# Exp_Board_RAMPS_0_1.net
KiCad netlist of a schematic drawn in EAGLE
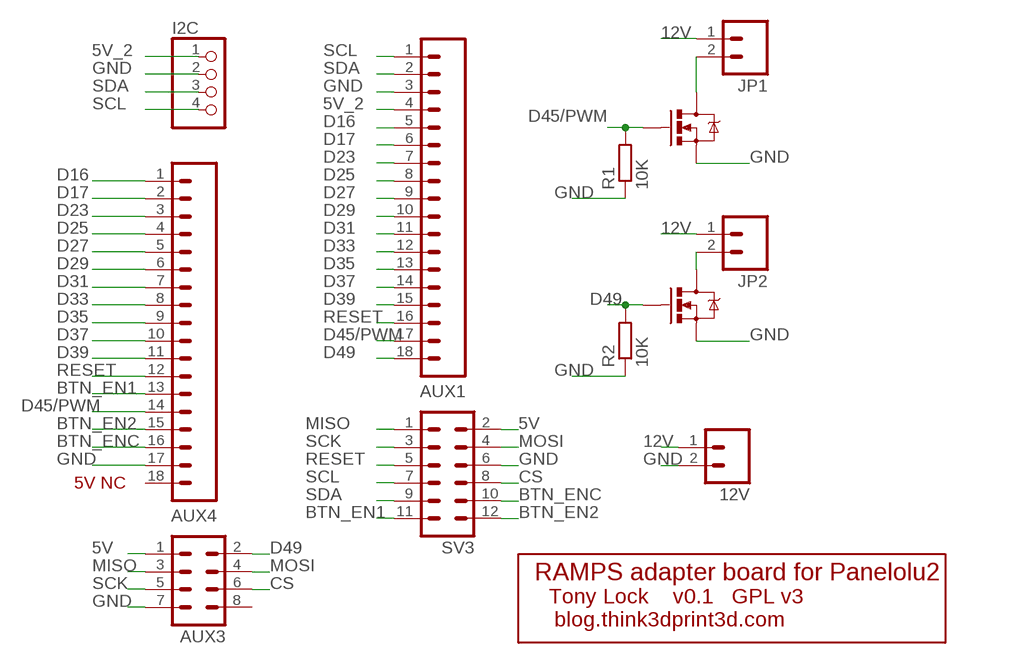
[diagram p0: schematic, sheet 1]

(export (version "E")
  (design (tool "Eeschema 10.0.6"))
  (components
    (comp (ref "12V")
      (value "M02PTH")
      (footprint "eagle-import:1X02")
      (libsource (lib "eagle-import") (part "M02PTH"))
    )
    (comp (ref "AUX1")
      (value "SPARKFUN_M18_")
      (footprint "eagle-import:SPARKFUN_1X18")
      (libsource (lib "eagle-import") (part "SPARKFUN_M18_"))
    )
    (comp (ref "AUX3")
      (value "MA04-2")
      (footprint "eagle-import:MA04-2")
      (libsource (lib "eagle-import") (part "MA04-2"))
    )
    (comp (ref "AUX4")
      (value "SPARKFUN_M18_")
      (footprint "eagle-import:SPARKFUN_1X18")
      (libsource (lib "eagle-import") (part "SPARKFUN_M18_"))
    )
    (comp (ref "I2C")
      (value "REPRAPJR_PINHD-1X4")
      (footprint "eagle-import:REPRAPJR_1X04")
      (libsource (lib "eagle-import") (part "REPRAPJR_PINHD-1X4"))
    )
    (comp (ref "JP1")
      (value "M02PTH")
      (footprint "eagle-import:1X02")
      (libsource (lib "eagle-import") (part "M02PTH"))
    )
    (comp (ref "JP2")
      (value "M02PTH")
      (footprint "eagle-import:1X02")
      (libsource (lib "eagle-import") (part "M02PTH"))
    )
    (comp (ref "Q1")
      (value "Transistor1")
      (footprint "eagle-import:TO220V")
      (libsource (lib "eagle-import") (part "MOSFET-NCHANNELPTH2"))
    )
    (comp (ref "Q2")
      (value "Transistor2")
      (footprint "eagle-import:TO220V")
      (libsource (lib "eagle-import") (part "MOSFET-NCHANNELPTH2"))
    )
    (comp (ref "R1")
      (value "10K")
      (footprint "eagle-import:0204_7")
      (libsource (lib "eagle-import") (part "R-EU_0204/7"))
    )
    (comp (ref "R2")
      (value "10K")
      (footprint "eagle-import:0204_7")
      (libsource (lib "eagle-import") (part "R-EU_0204/7"))
    )
    (comp (ref "SV3")
      (value "MA06-2_BACK")
      (footprint "eagle-import:MA06-2_BACK")
      (libsource (lib "eagle-import") (part "MA06-2_BACK"))
    )
  )
  (nets
    (net (code "1") (name "/5V") (class "Default")
      (node (ref "AUX3") (pin "1") (pinfunction "1_1") (pintype "passive"))
      (node (ref "SV3") (pin "2") (pinfunction "2_2") (pintype "passive"))
    )
    (net (code "2") (name "/5V_2") (class "Default")
      (node (ref "AUX1") (pin "4") (pinfunction "4_4") (pintype "passive"))
      (node (ref "I2C") (pin "1") (pinfunction "1_1") (pintype "passive"))
    )
    (net (code "3") (name "/12V") (class "Default")
      (node (ref "12V") (pin "1") (pinfunction "1_1") (pintype "passive"))
      (node (ref "JP1") (pin "1") (pinfunction "1_1") (pintype "passive"))
      (node (ref "JP2") (pin "1") (pinfunction "1_1") (pintype "passive"))
    )
    (net (code "4") (name "/BTN_EN1") (class "Default")
      (node (ref "AUX4") (pin "13") (pinfunction "13_13") (pintype "passive"))
      (node (ref "SV3") (pin "11") (pinfunction "11_11") (pintype "passive"))
    )
    (net (code "5") (name "/BTN_EN2") (class "Default")
      (node (ref "AUX4") (pin "15") (pinfunction "15_15") (pintype "passive"))
      (node (ref "SV3") (pin "12") (pinfunction "12_12") (pintype "passive"))
    )
    (net (code "6") (name "/BTN_ENC") (class "Default")
      (node (ref "AUX4") (pin "16") (pinfunction "16_16") (pintype "passive"))
      (node (ref "SV3") (pin "10") (pinfunction "10_10") (pintype "passive"))
    )
    (net (code "7") (name "/CS") (class "Default")
      (node (ref "AUX3") (pin "6") (pinfunction "6_6") (pintype "passive"))
      (node (ref "SV3") (pin "8") (pinfunction "8_8") (pintype "passive"))
    )
    (net (code "8") (name "/D16") (class "Default")
      (node (ref "AUX1") (pin "5") (pinfunction "5_5") (pintype "passive"))
      (node (ref "AUX4") (pin "1") (pinfunction "1_1") (pintype "passive"))
    )
    (net (code "9") (name "/D17") (class "Default")
      (node (ref "AUX1") (pin "6") (pinfunction "6_6") (pintype "passive"))
      (node (ref "AUX4") (pin "2") (pinfunction "2_2") (pintype "passive"))
    )
    (net (code "10") (name "/D23") (class "Default")
      (node (ref "AUX1") (pin "7") (pinfunction "7_7") (pintype "passive"))
      (node (ref "AUX4") (pin "3") (pinfunction "3_3") (pintype "passive"))
    )
    (net (code "11") (name "/D25") (class "Default")
      (node (ref "AUX1") (pin "8") (pinfunction "8_8") (pintype "passive"))
      (node (ref "AUX4") (pin "4") (pinfunction "4_4") (pintype "passive"))
    )
    (net (code "12") (name "/D27") (class "Default")
      (node (ref "AUX1") (pin "9") (pinfunction "9_9") (pintype "passive"))
      (node (ref "AUX4") (pin "5") (pinfunction "5_5") (pintype "passive"))
    )
    (net (code "13") (name "/D29") (class "Default")
      (node (ref "AUX1") (pin "10") (pinfunction "10_10") (pintype "passive"))
      (node (ref "AUX4") (pin "6") (pinfunction "6_6") (pintype "passive"))
    )
    (net (code "14") (name "/D31") (class "Default")
      (node (ref "AUX1") (pin "11") (pinfunction "11_11") (pintype "passive"))
      (node (ref "AUX4") (pin "7") (pinfunction "7_7") (pintype "passive"))
    )
    (net (code "15") (name "/D33") (class "Default")
      (node (ref "AUX1") (pin "12") (pinfunction "12_12") (pintype "passive"))
      (node (ref "AUX4") (pin "8") (pinfunction "8_8") (pintype "passive"))
    )
    (net (code "16") (name "/D35") (class "Default")
      (node (ref "AUX1") (pin "13") (pinfunction "13_13") (pintype "passive"))
      (node (ref "AUX4") (pin "9") (pinfunction "9_9") (pintype "passive"))
    )
    (net (code "17") (name "/D37") (class "Default")
      (node (ref "AUX1") (pin "14") (pinfunction "14_14") (pintype "passive"))
      (node (ref "AUX4") (pin "10") (pinfunction "10_10") (pintype "passive"))
    )
    (net (code "18") (name "/D39") (class "Default")
      (node (ref "AUX1") (pin "15") (pinfunction "15_15") (pintype "passive"))
      (node (ref "AUX4") (pin "11") (pinfunction "11_11") (pintype "passive"))
    )
    (net (code "19") (name "/D45{slash}PWM") (class "Default")
      (node (ref "AUX1") (pin "17") (pinfunction "17_17") (pintype "passive"))
      (node (ref "AUX4") (pin "14") (pinfunction "14_14") (pintype "passive"))
      (node (ref "Q1") (pin "1") (pinfunction "G_1") (pintype "passive"))
      (node (ref "R1") (pin "2") (pinfunction "2_2") (pintype "passive"))
    )
    (net (code "20") (name "/D49") (class "Default")
      (node (ref "AUX1") (pin "18") (pinfunction "18_18") (pintype "passive"))
      (node (ref "AUX3") (pin "2") (pinfunction "2_2") (pintype "passive"))
      (node (ref "Q2") (pin "1") (pinfunction "G_1") (pintype "passive"))
      (node (ref "R2") (pin "2") (pinfunction "2_2") (pintype "passive"))
    )
    (net (code "21") (name "/GND") (class "Default")
      (node (ref "12V") (pin "2") (pinfunction "2_2") (pintype "passive"))
      (node (ref "AUX1") (pin "3") (pinfunction "3_3") (pintype "passive"))
      (node (ref "AUX3") (pin "7") (pinfunction "7_7") (pintype "passive"))
      (node (ref "AUX4") (pin "17") (pinfunction "17_17") (pintype "passive"))
      (node (ref "I2C") (pin "2") (pinfunction "2_2") (pintype "passive"))
      (node (ref "Q1") (pin "3") (pinfunction "S_3") (pintype "passive"))
      (node (ref "Q2") (pin "3") (pinfunction "S_3") (pintype "passive"))
      (node (ref "R1") (pin "1") (pinfunction "1_1") (pintype "passive"))
      (node (ref "R2") (pin "1") (pinfunction "1_1") (pintype "passive"))
      (node (ref "SV3") (pin "6") (pinfunction "6_6") (pintype "passive"))
    )
    (net (code "22") (name "/MISO") (class "Default")
      (node (ref "AUX3") (pin "3") (pinfunction "3_3") (pintype "passive"))
      (node (ref "SV3") (pin "1") (pinfunction "1_1") (pintype "passive"))
    )
    (net (code "23") (name "/MOSI") (class "Default")
      (node (ref "AUX3") (pin "4") (pinfunction "4_4") (pintype "passive"))
      (node (ref "SV3") (pin "4") (pinfunction "4_4") (pintype "passive"))
    )
    (net (code "24") (name "/RESET") (class "Default")
      (node (ref "AUX1") (pin "16") (pinfunction "16_16") (pintype "passive"))
      (node (ref "AUX4") (pin "12") (pinfunction "12_12") (pintype "passive"))
      (node (ref "SV3") (pin "5") (pinfunction "5_5") (pintype "passive"))
    )
    (net (code "25") (name "/SCK") (class "Default")
      (node (ref "AUX3") (pin "5") (pinfunction "5_5") (pintype "passive"))
      (node (ref "SV3") (pin "3") (pinfunction "3_3") (pintype "passive"))
    )
    (net (code "26") (name "/SCL") (class "Default")
      (node (ref "AUX1") (pin "1") (pinfunction "1_1") (pintype "passive"))
      (node (ref "I2C") (pin "4") (pinfunction "4_4") (pintype "passive"))
      (node (ref "SV3") (pin "7") (pinfunction "7_7") (pintype "passive"))
    )
    (net (code "27") (name "/SDA") (class "Default")
      (node (ref "AUX1") (pin "2") (pinfunction "2_2") (pintype "passive"))
      (node (ref "I2C") (pin "3") (pinfunction "3_3") (pintype "passive"))
      (node (ref "SV3") (pin "9") (pinfunction "9_9") (pintype "passive"))
    )
    (net (code "28") (name "Net-(Q1-D)") (class "Default")
      (node (ref "JP1") (pin "2") (pinfunction "2_2") (pintype "passive"))
      (node (ref "Q1") (pin "2") (pinfunction "D_2") (pintype "passive"))
    )
    (net (code "29") (name "Net-(Q2-D)") (class "Default")
      (node (ref "JP2") (pin "2") (pinfunction "2_2") (pintype "passive"))
      (node (ref "Q2") (pin "2") (pinfunction "D_2") (pintype "passive"))
    )
    (net (code "30") (name "unconnected-(AUX3-Pad8)") (class "Default")
      (node (ref "AUX3") (pin "8") (pinfunction "8_8") (pintype "passive"))
    )
    (net (code "31") (name "unconnected-(AUX4-Pad18)") (class "Default")
      (node (ref "AUX4") (pin "18") (pinfunction "18_18") (pintype "passive"))
    )
  )
)
